# Power_Distribution.net
KiCad netlist of a schematic drawn in Altium Designer
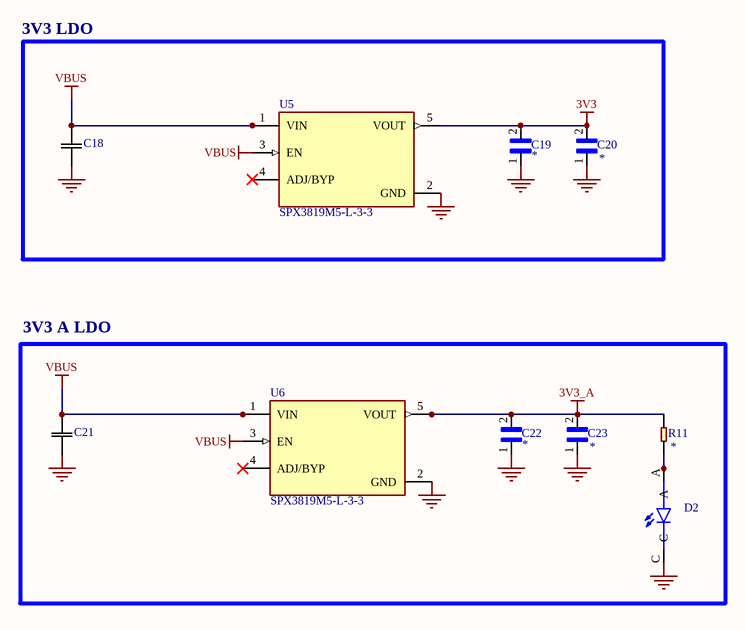
[diagram p0: Power Distribution.SchDoc]

(export (version "E")
  (design (tool "Eeschema 10.0.6"))
  (components
    (comp (ref "C18")
      (value "CC0201MRX5R6BB105")
      (footprint "CAP_CC0201_YAG")
      (description "No Description Available")
      (libsource (lib "CC0201MRX5R6BB105") (part "CC0201MRX5R6BB105"))
    )
    (comp (ref "C19")
      (value "GRM033R71A103KA01D")
      (footprint "CAPC0603X33N")
      (description "SMD Capacitor X7R(EIA) with Capacitance: 10000pF Tol. 10%. Rated Voltage: 10Vdc")
      (fields (field (name "ALTIUM_VALUE") "*") (field (name "MF") "Murata"))
      (libsource (lib "GRM033R71A103KA01D") (part "GRM033R71A103KA01D"))
    )
    (comp (ref "C20")
      (value "GRM155C80J225KE95D")
      (footprint "CAPC1005X55N")
      (description "2.2ÂµF Â±10% 6.3V Ceramic Capacitor X6S 0402 (1005 Metric)")
      (fields
        (field (name "DIGI-KEY_PART_NUMBER") "490-10012-1-ND")
        (field (name "ALTIUM_VALUE") "*")
        (field (name "MF") "Murata")
      )
      (libsource (lib "GRM155C80J225KE95D") (part "GRM155C80J225KE95D"))
    )
    (comp (ref "C21")
      (value "CC0201MRX5R6BB105")
      (footprint "CAP_CC0201_YAG")
      (description "No Description Available")
      (libsource (lib "CC0201MRX5R6BB105") (part "CC0201MRX5R6BB105"))
    )
    (comp (ref "C22")
      (value "GRM033R71A103KA01D")
      (footprint "CAPC0603X33N")
      (description "SMD Capacitor X7R(EIA) with Capacitance: 10000pF Tol. 10%. Rated Voltage: 10Vdc")
      (fields (field (name "ALTIUM_VALUE") "*") (field (name "MF") "Murata"))
      (libsource (lib "GRM033R71A103KA01D") (part "GRM033R71A103KA01D"))
    )
    (comp (ref "C23")
      (value "GRM155C80J225KE95D")
      (footprint "CAPC1005X55N")
      (description "2.2ÂµF Â±10% 6.3V Ceramic Capacitor X6S 0402 (1005 Metric)")
      (fields
        (field (name "DIGI-KEY_PART_NUMBER") "490-10012-1-ND")
        (field (name "ALTIUM_VALUE") "*")
        (field (name "MF") "Murata")
      )
      (libsource (lib "GRM155C80J225KE95D") (part "GRM155C80J225KE95D"))
    )
    (comp (ref "D2")
      (value "LTST-C190KFKT")
      (footprint "LEDM1608X80")
      (description "LED Uni-Color Orange 611nm 2-Pin Chip LED T/R")
      (fields (field (name "MF") "Lite-On Electronics"))
      (libsource (lib "LTST-C190KFKT") (part "LTST-C190KFKT"))
    )
    (comp (ref "R11")
      (value "SMD-RES-1K-5%-1/16W(0402)")
      (footprint "R0402")
      (description "1 kOhms Â±5% 0.063W, 1/16W Chip Resistor 0402 (1005 Metric) Moisture Resistant Thick Film")
      (fields
        (field (name "ALTIUM_VALUE") "*")
        (field (name "MP") "RC0402JR-071KL")
        (field (name "DIGI-KEY_PART_NUMBER") "311-1.0KJRTR-ND")
      )
      (libsource (lib "SMD-RES-1K-5_-1_16W_0402_") (part "SMD-RES-1K-5%-1/16W(0402)"))
    )
    (comp (ref "U5")
      (value "SPX3819M5-L-3-3")
      (footprint "SOT95P280X145-5N")
      (description "Linear Voltage Regulator IC Positive Fixed 1 Output 500mA SOT-23-5")
      (fields (field (name "MF") "MaxLinear, Inc.") (field (name "MP") "SPX3819M5-L-3-3/TR"))
      (libsource (lib "SPX3819M5-L-3-3") (part "SPX3819M5-L-3-3"))
    )
    (comp (ref "U6")
      (value "SPX3819M5-L-3-3")
      (footprint "SOT95P280X145-5N")
      (description "Linear Voltage Regulator IC Positive Fixed 1 Output 500mA SOT-23-5")
      (fields (field (name "MF") "MaxLinear, Inc.") (field (name "MP") "SPX3819M5-L-3-3/TR"))
      (libsource (lib "SPX3819M5-L-3-3") (part "SPX3819M5-L-3-3"))
    )
  )
  (nets
    (net (code "1") (name "3V3") (class "Default")
      (node (ref "C19") (pin "2") (pinfunction "2_2") (pintype "passive"))
      (node (ref "C20") (pin "2") (pinfunction "2_2") (pintype "passive"))
      (node (ref "U5") (pin "5") (pinfunction "VOUT_5") (pintype "output"))
    )
    (net (code "2") (name "3V3_A") (class "Default")
      (node (ref "C22") (pin "2") (pinfunction "2_2") (pintype "passive"))
      (node (ref "C23") (pin "2") (pinfunction "2_2") (pintype "passive"))
      (node (ref "R11") (pin "2") (pinfunction "2_2") (pintype "passive"))
      (node (ref "U6") (pin "5") (pinfunction "VOUT_5") (pintype "output"))
    )
    (net (code "3") (name "GND") (class "Default")
      (node (ref "C18") (pin "1") (pinfunction "1_1") (pintype "passive"))
      (node (ref "C19") (pin "1") (pinfunction "1_1") (pintype "passive"))
      (node (ref "C20") (pin "1") (pinfunction "1_1") (pintype "passive"))
      (node (ref "C21") (pin "1") (pinfunction "1_1") (pintype "passive"))
      (node (ref "C22") (pin "1") (pinfunction "1_1") (pintype "passive"))
      (node (ref "C23") (pin "1") (pinfunction "1_1") (pintype "passive"))
      (node (ref "D2") (pin "C") (pinfunction "C_C") (pintype "passive"))
      (node (ref "U5") (pin "2") (pinfunction "GND_2") (pintype "passive"))
      (node (ref "U6") (pin "2") (pinfunction "GND_2") (pintype "passive"))
    )
    (net (code "4") (name "Net-(D2-PadA)") (class "Default")
      (node (ref "D2") (pin "A") (pinfunction "A_A") (pintype "passive"))
      (node (ref "R11") (pin "1") (pinfunction "1_1") (pintype "passive"))
    )
    (net (code "5") (name "VBUS") (class "Default")
      (node (ref "C18") (pin "2") (pinfunction "2_2") (pintype "passive"))
      (node (ref "C21") (pin "2") (pinfunction "2_2") (pintype "passive"))
      (node (ref "U5") (pin "1") (pinfunction "VIN_1") (pintype "power_in"))
      (node (ref "U5") (pin "3") (pinfunction "EN_3") (pintype "input"))
      (node (ref "U6") (pin "1") (pinfunction "VIN_1") (pintype "power_in"))
      (node (ref "U6") (pin "3") (pinfunction "EN_3") (pintype "input"))
    )
    (net (code "6") (name "unconnected-(U5-ADJ{slash}BYP-Pad4)") (class "Default")
      (node (ref "U5") (pin "4") (pinfunction "ADJ/BYP_4") (pintype "passive+no_connect"))
    )
    (net (code "7") (name "unconnected-(U6-ADJ{slash}BYP-Pad4)") (class "Default")
      (node (ref "U6") (pin "4") (pinfunction "ADJ/BYP_4") (pintype "passive+no_connect"))
    )
  )
)
